# Buzzer.net
KiCad netlist of a schematic drawn in Altium Designer
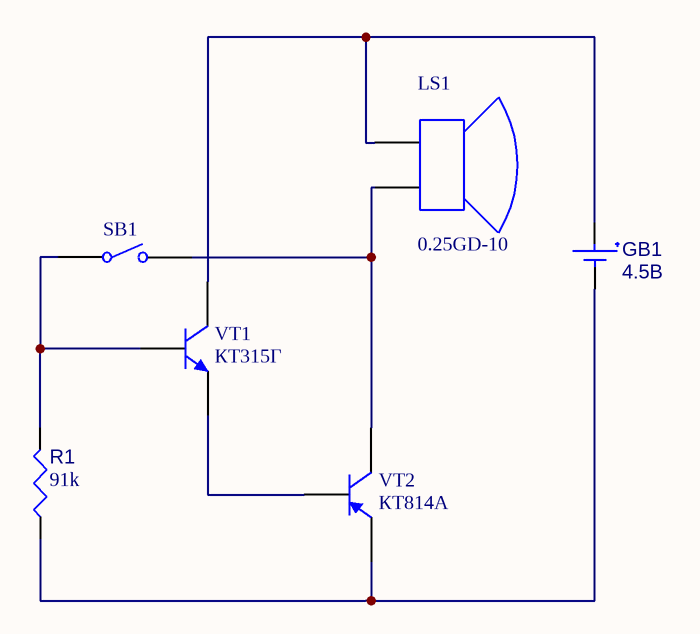
[diagram p0: Buzzer.SchDoc]

(export (version "E")
  (design (tool "Eeschema 10.0.6"))
  (components
    (comp (ref "GB1")
      (value "4.5B")
      (footprint "SEIK-MS621FE-FL11E-2_V")
      (description "MS Lihium Rechargeable Battery, 3 V, -20 to 60 degC, Tray")
      (libsource (lib "Yurchenko 20031208") (part "CMP-00622-2"))
    )
    (comp (ref "LS1")
      (value "0.25GD-10")
      (footprint "ADAI-ADA1898")
      (description "Mini Speaker, 8 Ohm, 0.2 Wmax, -10 to 40 degC, 2-Pin THD, RoHS")
      (fields (field (name "MANUFACTURER") "Adafruit Industries"))
      (libsource (lib "Yurchenko 20031208") (part "SPEAKER-2"))
    )
    (comp (ref "R1")
      (value "91k")
      (footprint "RESC0805(2012)_L")
      (description "1K 0.125W 5% 0805 (2012 Metric)  SMD")
      (fields (field (name "TOLERANCE") "5%") (field (name "POWER") "125mW"))
      (libsource (lib "Yurchenko 20031208") (part "1KR5J"))
    )
    (comp (ref "SB1")
      (value "B3U-3000P")
      (footprint "OMRON-B3U-3000P_V")
      (description "Tactile Switch, SPST-NO, 0.05 A, 12 V, -25 to 70 degC, 2-Pin SMD, RoHS, Tape and Reel")
      (fields (field (name "MANUFACTURER") "Omron Electronic Components"))
      (libsource (lib "Yurchenko 20031208") (part "SW-SPST-2_C"))
    )
    (comp (ref "VT1")
      (value "КТ315Г")
      (footprint "JSCJ-TO-92-3_V")
      (description "Transistor, NPN, 0.1 uA, 150 MHz, 3-Pin TO-92")
      (fields (field (name "MANUFACTURER") "Jiangsu Changjiang Electronics Technology"))
      (libsource (lib "Yurchenko 20031208") (part "BJT-NPN-EBC-3"))
    )
    (comp (ref "VT2")
      (value "КТ814А")
      (footprint "UNIC-TO-92-3")
      (description "Low Voltage High Current Small Signal PNP Transistor, 20 V, 700 mA, 3-Pin TO-92, RoHS")
      (fields (field (name "MANUFACTURER") "Unisonic"))
      (libsource (lib "Yurchenko 20031208") (part "BJT-PNP-EBC-3"))
    )
  )
  (nets
    (net (code "1") (name "Net-(GB1-+)") (class "Default")
      (node (ref "GB1") (pin "1") (pinfunction "+_1") (pintype "passive"))
      (node (ref "LS1") (pin "1") (pinfunction "+_1") (pintype "passive"))
      (node (ref "VT1") (pin "3") (pinfunction "C_3") (pintype "passive"))
    )
    (net (code "2") (name "Net-(GB1--)") (class "Default")
      (node (ref "GB1") (pin "2") (pinfunction "-_2") (pintype "passive"))
      (node (ref "R1") (pin "1") (pinfunction "1_1") (pintype "passive"))
      (node (ref "VT2") (pin "1") (pinfunction "E_1") (pintype "passive"))
    )
    (net (code "3") (name "Net-(LS1--)") (class "Default")
      (node (ref "LS1") (pin "2") (pinfunction "-_2") (pintype "passive"))
      (node (ref "SB1") (pin "2") (pinfunction "2_2") (pintype "passive"))
      (node (ref "VT2") (pin "3") (pinfunction "C_3") (pintype "passive"))
    )
    (net (code "4") (name "Net-(VT1-B)") (class "Default")
      (node (ref "R1") (pin "2") (pinfunction "2_2") (pintype "passive"))
      (node (ref "SB1") (pin "1") (pinfunction "1_1") (pintype "passive"))
      (node (ref "VT1") (pin "2") (pinfunction "B_2") (pintype "passive"))
    )
    (net (code "5") (name "Net-(VT1-E)") (class "Default")
      (node (ref "VT1") (pin "1") (pinfunction "E_1") (pintype "passive"))
      (node (ref "VT2") (pin "2") (pinfunction "B_2") (pintype "passive"))
    )
  )
)
